# chip.net
KiCad netlist of a schematic drawn in EAGLE
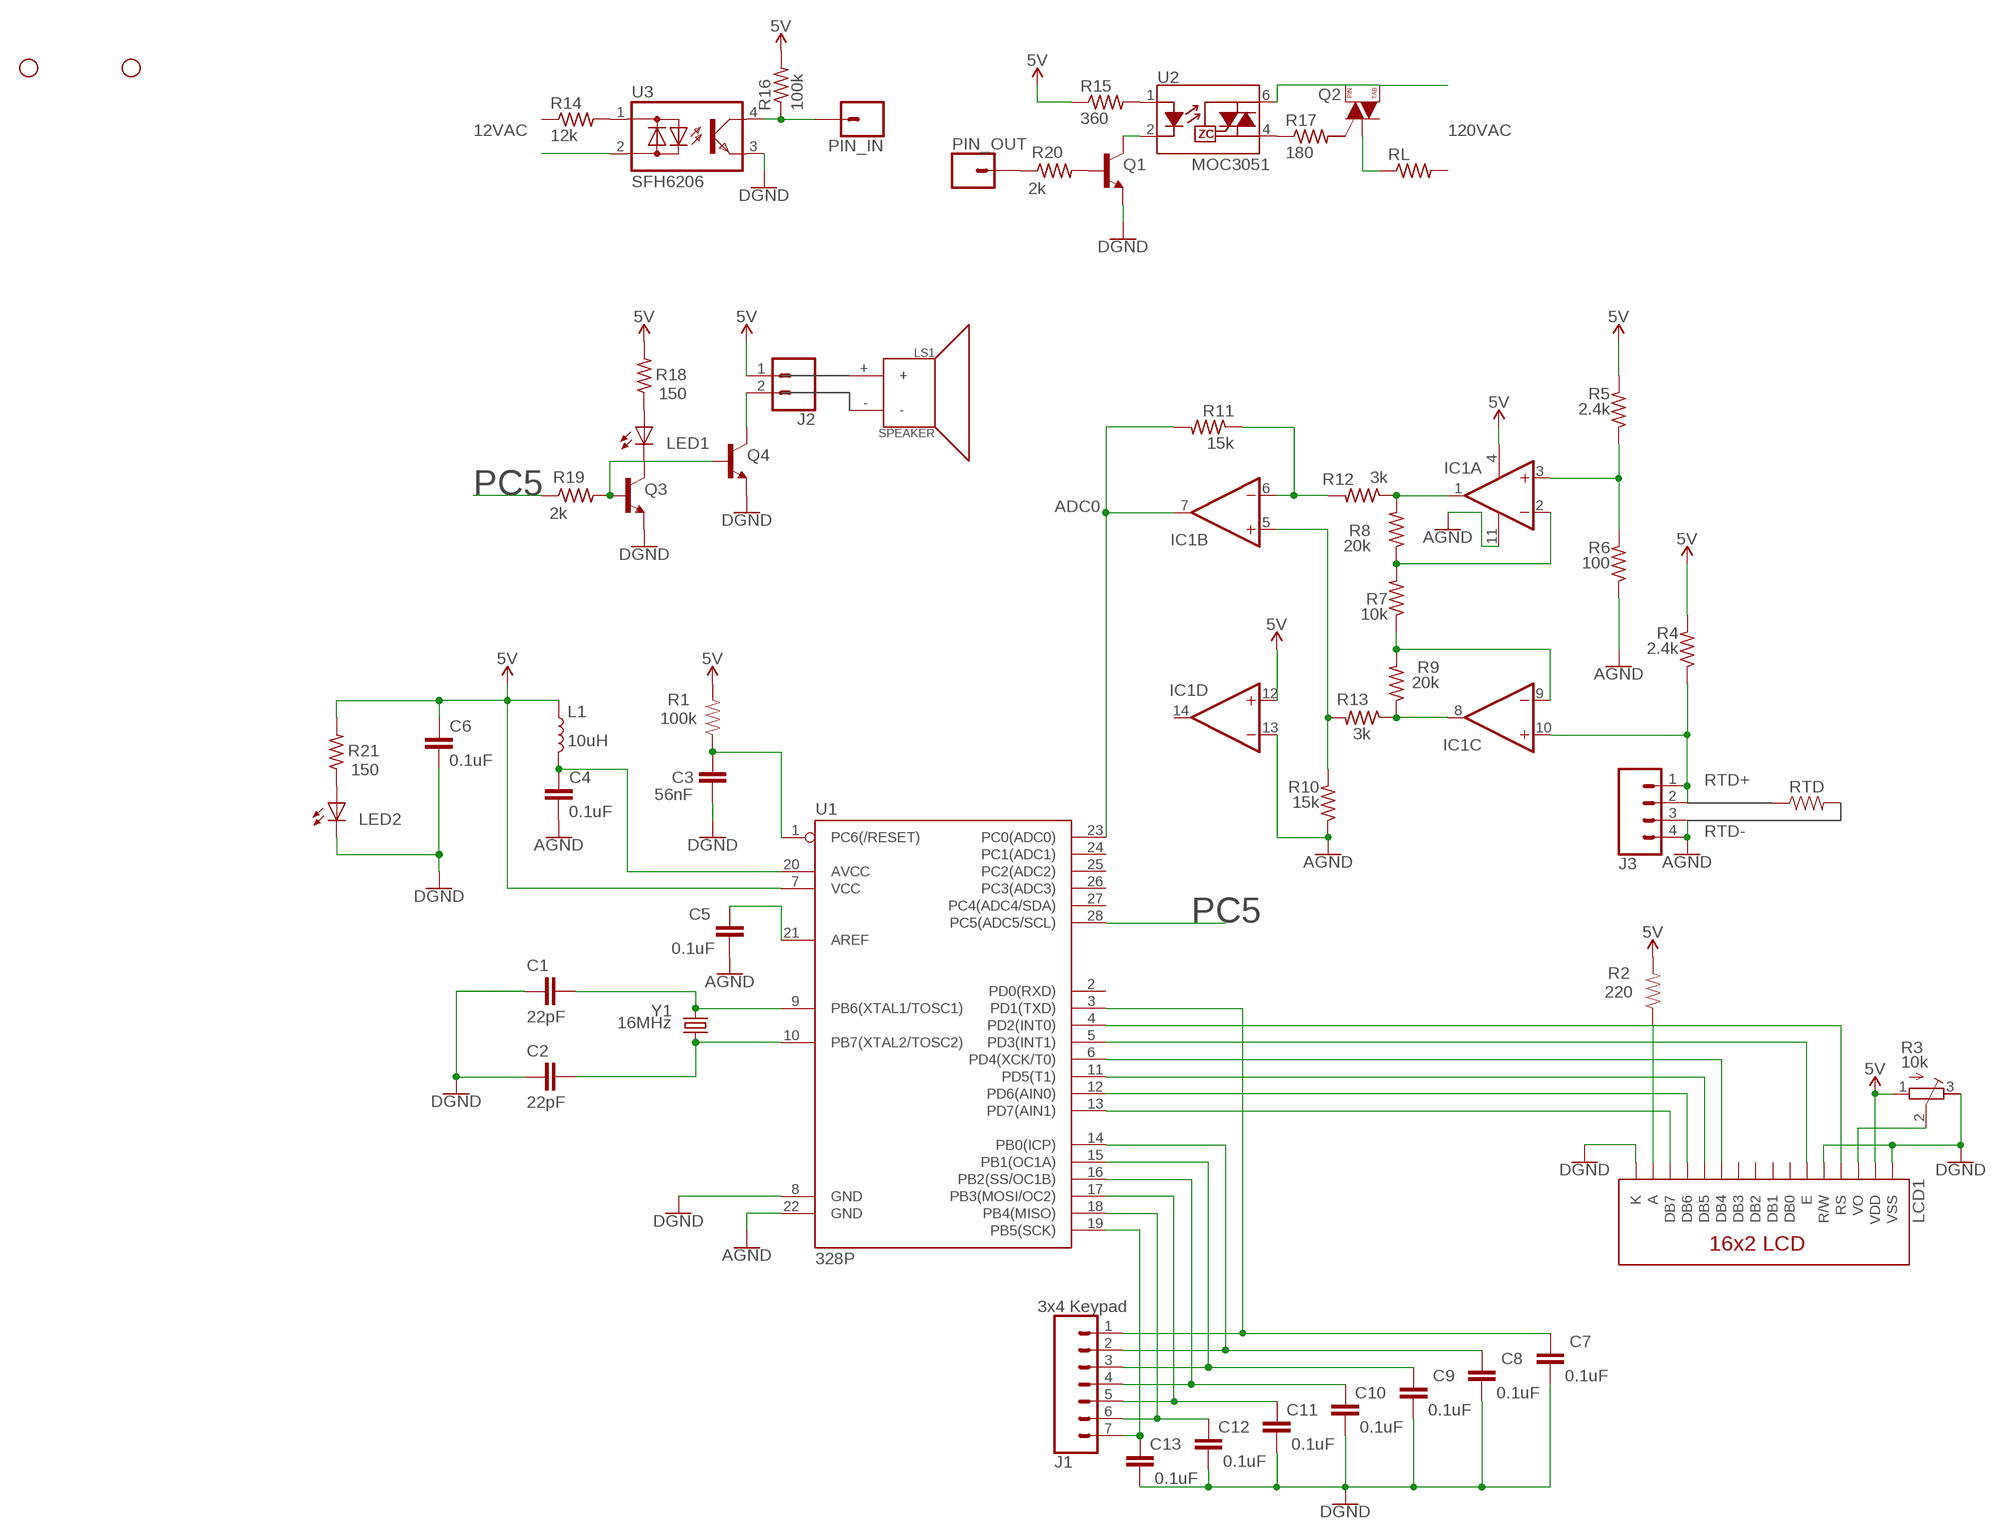
[diagram p0: schematic, sheet 1]

(export (version "E")
  (design (tool "Eeschema 10.0.6"))
  (components
    (comp (ref "C1")
      (value "22pF")
      (footprint "eagle-import:0603")
      (libsource (lib "eagle-import") (part "22PF-0603-50V-5%"))
    )
    (comp (ref "C2")
      (value "22pF")
      (footprint "eagle-import:0603")
      (libsource (lib "eagle-import") (part "22PF-0603-50V-5%"))
    )
    (comp (ref "C3")
      (value "56nF")
      (footprint "eagle-import:0603")
      (libsource (lib "eagle-import") (part "47NF-0603-25V-5%"))
    )
    (comp (ref "C4")
      (value "0.1uF")
      (footprint "eagle-import:0603")
      (libsource (lib "eagle-import") (part "0.1UF-0603-25V-(+80/-20%)"))
    )
    (comp (ref "C5")
      (value "0.1uF")
      (footprint "eagle-import:0603")
      (libsource (lib "eagle-import") (part "0.1UF-0603-25V-(+80/-20%)"))
    )
    (comp (ref "C6")
      (value "0.1uF")
      (footprint "eagle-import:0603")
      (libsource (lib "eagle-import") (part "0.1UF-0603-25V-(+80/-20%)"))
    )
    (comp (ref "C7")
      (value "0.1uF")
      (footprint "eagle-import:0603")
      (libsource (lib "eagle-import") (part "0.1UF-0603-25V-(+80/-20%)"))
    )
    (comp (ref "C8")
      (value "0.1uF")
      (footprint "eagle-import:0603")
      (libsource (lib "eagle-import") (part "0.1UF-0603-25V-(+80/-20%)"))
    )
    (comp (ref "C9")
      (value "0.1uF")
      (footprint "eagle-import:0603")
      (libsource (lib "eagle-import") (part "0.1UF-0603-25V-(+80/-20%)"))
    )
    (comp (ref "C10")
      (value "0.1uF")
      (footprint "eagle-import:0603")
      (libsource (lib "eagle-import") (part "0.1UF-0603-25V-(+80/-20%)"))
    )
    (comp (ref "C11")
      (value "0.1uF")
      (footprint "eagle-import:0603")
      (libsource (lib "eagle-import") (part "0.1UF-0603-25V-(+80/-20%)"))
    )
    (comp (ref "C12")
      (value "0.1uF")
      (footprint "eagle-import:0603")
      (libsource (lib "eagle-import") (part "0.1UF-0603-25V-(+80/-20%)"))
    )
    (comp (ref "C13")
      (value "0.1uF")
      (footprint "eagle-import:0603")
      (libsource (lib "eagle-import") (part "0.1UF-0603-25V-(+80/-20%)"))
    )
    (comp (ref "H10")
      (value "STAND-OFF")
      (footprint "eagle-import:STAND-OFF")
      (libsource (lib "eagle-import") (part "STAND-OFF"))
    )
    (comp (ref "H11")
      (value "STAND-OFF")
      (footprint "eagle-import:STAND-OFF")
      (libsource (lib "eagle-import") (part "STAND-OFF"))
    )
    (comp (ref "IC1")
      (value "MCP604SL")
      (footprint "eagle-import:SO14")
      (libsource (lib "eagle-import") (part "MCP604SL"))
    )
    (comp (ref "J1")
      (value "3x4 Keypad")
      (footprint "eagle-import:1X07")
      (libsource (lib "eagle-import") (part "CONN_07"))
    )
    (comp (ref "J2")
      (value "CONN_02")
      (footprint "eagle-import:1X02")
      (libsource (lib "eagle-import") (part "CONN_02"))
    )
    (comp (ref "J3")
      (value "CONN_04SCREW")
      (footprint "eagle-import:SCREWTERMINAL-3.5MM-4")
      (libsource (lib "eagle-import") (part "CONN_04SCREW"))
    )
    (comp (ref "L1")
      (value "10uH")
      (footprint "eagle-import:0603")
      (libsource (lib "eagle-import") (part "INDUCTOR-0603-33NH"))
    )
    (comp (ref "LCD1")
      (value "LCD-16X2NOHOLES")
      (footprint "eagle-import:LCD-16X2_NOHOLESNOSILK")
      (libsource (lib "eagle-import") (part "LCD-16X2NOHOLES"))
    )
    (comp (ref "LED1")
      (value "LED5MM")
      (footprint "eagle-import:LED5MM")
      (libsource (lib "eagle-import") (part "LED5MM"))
    )
    (comp (ref "LED2")
      (value "LED5MM")
      (footprint "eagle-import:LED5MM")
      (libsource (lib "eagle-import") (part "LED5MM"))
    )
    (comp (ref "LS1")
      (value "SPEAKER")
      (footprint "eagle-import:PCB_MOUNT_SPEAKER")
      (libsource (lib "eagle-import") (part "SPEAKER"))
    )
    (comp (ref "PIN_IN")
      (value "CONN_01")
      (footprint "eagle-import:1X01")
      (libsource (lib "eagle-import") (part "CONN_01"))
    )
    (comp (ref "PIN_OUT")
      (value "CONN_01")
      (footprint "eagle-import:1X01")
      (libsource (lib "eagle-import") (part "CONN_01"))
    )
    (comp (ref "Q1")
      (value "TRANS_NPN-MMBTA42")
      (footprint "eagle-import:SOT23-3")
      (libsource (lib "eagle-import") (part "TRANS_NPN-MMBTA42"))
    )
    (comp (ref "Q2")
      (value "BT137-600E")
      (footprint "eagle-import:SOT223")
      (libsource (lib "eagle-import") (part "TRIAC-Z0103MN"))
    )
    (comp (ref "Q3")
      (value "TRANS_NPN-MMBTA42")
      (footprint "eagle-import:SOT23-3")
      (libsource (lib "eagle-import") (part "TRANS_NPN-MMBTA42"))
    )
    (comp (ref "Q4")
      (value "TRANS_NPN-MMBTA42")
      (footprint "eagle-import:SOT23-3")
      (libsource (lib "eagle-import") (part "TRANS_NPN-MMBTA42"))
    )
    (comp (ref "R1")
      (value "100k")
      (footprint "eagle-import:0603")
      (libsource (lib "eagle-import") (part "10KOHM-0603-1/10W-1%"))
    )
    (comp (ref "R2")
      (value "220")
      (footprint "eagle-import:0603")
      (libsource (lib "eagle-import") (part "220OHM-0603-1/10W-1%"))
    )
    (comp (ref "R3")
      (value "10k")
      (footprint "eagle-import:RTRIM3296W")
      (libsource (lib "eagle-import") (part "R-TRIMM3296W"))
    )
    (comp (ref "R4")
      (value "2.4k")
      (footprint "eagle-import:R0603")
      (libsource (lib "eagle-import") (part "resistor_348_R-US_R0603"))
    )
    (comp (ref "R5")
      (value "2.4k")
      (footprint "eagle-import:R0603")
      (libsource (lib "eagle-import") (part "resistor_348_R-US_R0603"))
    )
    (comp (ref "R6")
      (value "100")
      (footprint "eagle-import:R0603")
      (libsource (lib "eagle-import") (part "resistor_348_R-US_R0603"))
    )
    (comp (ref "R7")
      (value "10k")
      (footprint "eagle-import:R0603")
      (libsource (lib "eagle-import") (part "resistor_348_R-US_R0603"))
    )
    (comp (ref "R8")
      (value "20k")
      (footprint "eagle-import:R0603")
      (libsource (lib "eagle-import") (part "resistor_348_R-US_R0603"))
    )
    (comp (ref "R9")
      (value "20k")
      (footprint "eagle-import:R0603")
      (libsource (lib "eagle-import") (part "resistor_348_R-US_R0603"))
    )
    (comp (ref "R10")
      (value "15k")
      (footprint "eagle-import:R0603")
      (libsource (lib "eagle-import") (part "resistor_348_R-US_R0603"))
    )
    (comp (ref "R11")
      (value "15k")
      (footprint "eagle-import:R0603")
      (libsource (lib "eagle-import") (part "resistor_348_R-US_R0603"))
    )
    (comp (ref "R12")
      (value "3k")
      (footprint "eagle-import:R0603")
      (libsource (lib "eagle-import") (part "resistor_348_R-US_R0603"))
    )
    (comp (ref "R13")
      (value "3k")
      (footprint "eagle-import:R0603")
      (libsource (lib "eagle-import") (part "resistor_348_R-US_R0603"))
    )
    (comp (ref "R14")
      (value "12k")
      (footprint "eagle-import:R0603")
      (libsource (lib "eagle-import") (part "R-US_R0603"))
    )
    (comp (ref "R15")
      (value "360")
      (footprint "eagle-import:R0603")
      (libsource (lib "eagle-import") (part "R-US_R0603"))
    )
    (comp (ref "R16")
      (value "100k")
      (footprint "eagle-import:R0603")
      (libsource (lib "eagle-import") (part "R-US_R0603"))
    )
    (comp (ref "R17")
      (value "180")
      (footprint "eagle-import:R0603")
      (libsource (lib "eagle-import") (part "R-US_R0603"))
    )
    (comp (ref "R18")
      (value "150")
      (footprint "eagle-import:R0603")
      (libsource (lib "eagle-import") (part "R-US_R0603"))
    )
    (comp (ref "R19")
      (value "2k")
      (footprint "eagle-import:R0603")
      (libsource (lib "eagle-import") (part "R-US_R0603"))
    )
    (comp (ref "R20")
      (value "2k")
      (footprint "eagle-import:R0603")
      (libsource (lib "eagle-import") (part "R-US_R0603"))
    )
    (comp (ref "R21")
      (value "150")
      (footprint "eagle-import:R0603")
      (libsource (lib "eagle-import") (part "R-US_R0603"))
    )
    (comp (ref "RL")
      (value "R-US_R0603")
      (footprint "eagle-import:R0603")
      (libsource (lib "eagle-import") (part "R-US_R0603"))
    )
    (comp (ref "RTD")
      (value "10KOHM-HORIZ-1/4W-1%")
      (footprint "eagle-import:AXIAL-0.3")
      (libsource (lib "eagle-import") (part "10KOHM-HORIZ-1/4W-1%"))
    )
    (comp (ref "U1")
      (value "328P")
      (footprint "eagle-import:DIP28")
      (libsource (lib "eagle-import") (part "ATMEGA328P_PDIP"))
    )
    (comp (ref "U2")
      (value "TRIAC_OPTOCOUPLER-MOC3063SM")
      (footprint "eagle-import:DIP8SMD")
      (libsource (lib "eagle-import") (part "TRIAC_OPTOCOUPLER-MOC3063SM"))
    )
    (comp (ref "U3")
      (value "SFH6206")
      (footprint "eagle-import:DIL4-SMD")
      (fields (field (name "MF") "VISHAY/TELEFUNKEN") (field (name "MPN") "SFH6206-3"))
      (libsource (lib "eagle-import") (part "SFH6206"))
    )
    (comp (ref "Y1")
      (value "16MHz")
      (footprint "eagle-import:HC49US")
      (libsource (lib "eagle-import") (part "CRYSTAL-16MHZPTH-HC49US"))
    )
  )
  (nets
    (net (code "1") (name "5V") (class "Default")
      (node (ref "C6") (pin "1") (pinfunction "1_1") (pintype "passive"))
      (node (ref "IC1") (pin "12") (pinfunction "+IN_12") (pintype "input"))
      (node (ref "IC1") (pin "4") (pinfunction "V+_4") (pintype "power_in"))
      (node (ref "J2") (pin "1") (pinfunction "1_1") (pintype "passive"))
      (node (ref "L1") (pin "1") (pinfunction "1_1") (pintype "passive"))
      (node (ref "LCD1") (pin "2") (pinfunction "VDD_2") (pintype "power_in"))
      (node (ref "R1") (pin "2") (pinfunction "2_2") (pintype "passive"))
      (node (ref "R15") (pin "1") (pinfunction "1_1") (pintype "passive"))
      (node (ref "R16") (pin "2") (pinfunction "2_2") (pintype "passive"))
      (node (ref "R18") (pin "2") (pinfunction "2_2") (pintype "passive"))
      (node (ref "R2") (pin "2") (pinfunction "2_2") (pintype "passive"))
      (node (ref "R21") (pin "2") (pinfunction "2_2") (pintype "passive"))
      (node (ref "R3") (pin "1") (pinfunction "A_1") (pintype "passive"))
      (node (ref "R4") (pin "2") (pinfunction "2_2") (pintype "passive"))
      (node (ref "R5") (pin "2") (pinfunction "2_2") (pintype "passive"))
      (node (ref "U1") (pin "7") (pinfunction "VCC_7") (pintype "bidirectional"))
    )
    (net (code "2") (name "AGND") (class "Default")
      (node (ref "C4") (pin "2") (pinfunction "2_2") (pintype "passive"))
      (node (ref "C5") (pin "2") (pinfunction "2_2") (pintype "passive"))
      (node (ref "IC1") (pin "11") (pinfunction "V-_11") (pintype "power_in"))
      (node (ref "IC1") (pin "13") (pinfunction "-IN_13") (pintype "input"))
      (node (ref "J3") (pin "3") (pinfunction "3_3") (pintype "passive"))
      (node (ref "J3") (pin "4") (pinfunction "4_4") (pintype "passive"))
      (node (ref "R10") (pin "1") (pinfunction "1_1") (pintype "passive"))
      (node (ref "R6") (pin "1") (pinfunction "1_1") (pintype "passive"))
      (node (ref "U1") (pin "22") (pinfunction "GND_22") (pintype "bidirectional"))
    )
    (net (code "3") (name "DGND") (class "Default")
      (node (ref "C1") (pin "1") (pinfunction "1_1") (pintype "passive"))
      (node (ref "C10") (pin "2") (pinfunction "2_2") (pintype "passive"))
      (node (ref "C11") (pin "2") (pinfunction "2_2") (pintype "passive"))
      (node (ref "C12") (pin "2") (pinfunction "2_2") (pintype "passive"))
      (node (ref "C13") (pin "2") (pinfunction "2_2") (pintype "passive"))
      (node (ref "C2") (pin "1") (pinfunction "1_1") (pintype "passive"))
      (node (ref "C3") (pin "2") (pinfunction "2_2") (pintype "passive"))
      (node (ref "C6") (pin "2") (pinfunction "2_2") (pintype "passive"))
      (node (ref "C7") (pin "2") (pinfunction "2_2") (pintype "passive"))
      (node (ref "C8") (pin "2") (pinfunction "2_2") (pintype "passive"))
      (node (ref "C9") (pin "2") (pinfunction "2_2") (pintype "passive"))
      (node (ref "LCD1") (pin "1") (pinfunction "VSS_1") (pintype "power_in"))
      (node (ref "LCD1") (pin "16") (pinfunction "K_16") (pintype "power_in"))
      (node (ref "LCD1") (pin "5") (pinfunction "R/W_5") (pintype "input"))
      (node (ref "LED2") (pin "K") (pinfunction "C_K") (pintype "passive"))
      (node (ref "Q1") (pin "2") (pinfunction "E_2") (pintype "passive"))
      (node (ref "Q3") (pin "2") (pinfunction "E_2") (pintype "passive"))
      (node (ref "Q4") (pin "2") (pinfunction "E_2") (pintype "passive"))
      (node (ref "R3") (pin "3") (pinfunction "E_3") (pintype "passive"))
      (node (ref "U1") (pin "8") (pinfunction "GND_8") (pintype "bidirectional"))
      (node (ref "U3") (pin "3") (pinfunction "E_3") (pintype "passive"))
    )
    (net (code "4") (name "Net-(IC1A-+IN)") (class "Default")
      (node (ref "IC1") (pin "3") (pinfunction "+IN_3") (pintype "input"))
      (node (ref "R5") (pin "1") (pinfunction "1_1") (pintype "passive"))
      (node (ref "R6") (pin "2") (pinfunction "2_2") (pintype "passive"))
    )
    (net (code "5") (name "Net-(IC1A--IN)") (class "Default")
      (node (ref "IC1") (pin "2") (pinfunction "-IN_2") (pintype "input"))
      (node (ref "R7") (pin "2") (pinfunction "2_2") (pintype "passive"))
      (node (ref "R8") (pin "1") (pinfunction "1_1") (pintype "passive"))
    )
    (net (code "6") (name "Net-(IC1A-OUT)") (class "Default")
      (node (ref "IC1") (pin "1") (pinfunction "OUT_1") (pintype "output"))
      (node (ref "R12") (pin "1") (pinfunction "1_1") (pintype "passive"))
      (node (ref "R8") (pin "2") (pinfunction "2_2") (pintype "passive"))
    )
    (net (code "7") (name "Net-(IC1B-+IN)") (class "Default")
      (node (ref "IC1") (pin "5") (pinfunction "+IN_5") (pintype "input"))
      (node (ref "R10") (pin "2") (pinfunction "2_2") (pintype "passive"))
      (node (ref "R13") (pin "2") (pinfunction "2_2") (pintype "passive"))
    )
    (net (code "8") (name "Net-(IC1B--IN)") (class "Default")
      (node (ref "IC1") (pin "6") (pinfunction "-IN_6") (pintype "input"))
      (node (ref "R11") (pin "1") (pinfunction "1_1") (pintype "passive"))
      (node (ref "R12") (pin "2") (pinfunction "2_2") (pintype "passive"))
    )
    (net (code "9") (name "Net-(IC1B-OUT)") (class "Default")
      (node (ref "IC1") (pin "7") (pinfunction "OUT_7") (pintype "output"))
      (node (ref "R11") (pin "2") (pinfunction "2_2") (pintype "passive"))
      (node (ref "U1") (pin "23") (pinfunction "PC0(ADC0)_23") (pintype "bidirectional"))
    )
    (net (code "10") (name "Net-(IC1C-+IN)") (class "Default")
      (node (ref "IC1") (pin "10") (pinfunction "+IN_10") (pintype "input"))
      (node (ref "J3") (pin "1") (pinfunction "1_1") (pintype "passive"))
      (node (ref "J3") (pin "2") (pinfunction "2_2") (pintype "passive"))
      (node (ref "R4") (pin "1") (pinfunction "1_1") (pintype "passive"))
    )
    (net (code "11") (name "Net-(IC1C--IN)") (class "Default")
      (node (ref "IC1") (pin "9") (pinfunction "-IN_9") (pintype "input"))
      (node (ref "R7") (pin "1") (pinfunction "1_1") (pintype "passive"))
      (node (ref "R9") (pin "2") (pinfunction "2_2") (pintype "passive"))
    )
    (net (code "12") (name "Net-(IC1C-OUT)") (class "Default")
      (node (ref "IC1") (pin "8") (pinfunction "OUT_8") (pintype "output"))
      (node (ref "R13") (pin "1") (pinfunction "1_1") (pintype "passive"))
      (node (ref "R9") (pin "1") (pinfunction "1_1") (pintype "passive"))
    )
    (net (code "13") (name "Net-(LCD1-A)") (class "Default")
      (node (ref "LCD1") (pin "15") (pinfunction "A_15") (pintype "power_in"))
      (node (ref "R2") (pin "1") (pinfunction "1_1") (pintype "passive"))
    )
    (net (code "14") (name "Net-(LCD1-DB4)") (class "Default")
      (node (ref "LCD1") (pin "11") (pinfunction "DB4_11") (pintype "bidirectional"))
      (node (ref "U1") (pin "6") (pinfunction "PD4(XCK/T0)_6") (pintype "bidirectional"))
    )
    (net (code "15") (name "Net-(LCD1-DB5)") (class "Default")
      (node (ref "LCD1") (pin "12") (pinfunction "DB5_12") (pintype "bidirectional"))
      (node (ref "U1") (pin "11") (pinfunction "PD5(T1)_11") (pintype "bidirectional"))
    )
    (net (code "16") (name "Net-(LCD1-DB6)") (class "Default")
      (node (ref "LCD1") (pin "13") (pinfunction "DB6_13") (pintype "bidirectional"))
      (node (ref "U1") (pin "12") (pinfunction "PD6(AIN0)_12") (pintype "bidirectional"))
    )
    (net (code "17") (name "Net-(LCD1-DB7)") (class "Default")
      (node (ref "LCD1") (pin "14") (pinfunction "DB7_14") (pintype "bidirectional"))
      (node (ref "U1") (pin "13") (pinfunction "PD7(AIN1)_13") (pintype "bidirectional"))
    )
    (net (code "18") (name "Net-(LCD1-E)") (class "Default")
      (node (ref "LCD1") (pin "6") (pinfunction "E_6") (pintype "input"))
      (node (ref "U1") (pin "5") (pinfunction "PD3(INT1)_5") (pintype "bidirectional"))
    )
    (net (code "19") (name "Net-(LCD1-RS)") (class "Default")
      (node (ref "LCD1") (pin "4") (pinfunction "RS_4") (pintype "input"))
      (node (ref "U1") (pin "4") (pinfunction "PD2(INT0)_4") (pintype "bidirectional"))
    )
    (net (code "20") (name "Net-(LCD1-VO)") (class "Default")
      (node (ref "LCD1") (pin "3") (pinfunction "VO_3") (pintype "bidirectional"))
      (node (ref "R3") (pin "2") (pinfunction "S_2") (pintype "passive"))
    )
    (net (code "21") (name "Net-(LED1-C)") (class "Default")
      (node (ref "LED1") (pin "K") (pinfunction "C_K") (pintype "passive"))
      (node (ref "Q3") (pin "3") (pinfunction "C_3") (pintype "passive"))
    )
    (net (code "22") (name "Net-(LED1-PadA)") (class "Default")
      (node (ref "LED1") (pin "A") (pinfunction "A_A") (pintype "passive"))
      (node (ref "R18") (pin "1") (pinfunction "1_1") (pintype "passive"))
    )
    (net (code "23") (name "Net-(LED2-PadA)") (class "Default")
      (node (ref "LED2") (pin "A") (pinfunction "A_A") (pintype "passive"))
      (node (ref "R21") (pin "1") (pinfunction "1_1") (pintype "passive"))
    )
    (net (code "24") (name "Net-(PIN_OUT-Pad1)") (class "Default")
      (node (ref "PIN_OUT") (pin "1") (pinfunction "1_1") (pintype "passive"))
      (node (ref "R20") (pin "1") (pinfunction "1_1") (pintype "passive"))
    )
    (net (code "25") (name "Net-(Q1-B)") (class "Default")
      (node (ref "Q1") (pin "1") (pinfunction "B_1") (pintype "passive"))
      (node (ref "R20") (pin "2") (pinfunction "2_2") (pintype "passive"))
    )
    (net (code "26") (name "Net-(Q1-C)") (class "Default")
      (node (ref "Q1") (pin "3") (pinfunction "C_3") (pintype "passive"))
      (node (ref "U2") (pin "2") (pinfunction "K_2") (pintype "bidirectional"))
    )
    (net (code "27") (name "Net-(Q2-T1)") (class "Default")
      (node (ref "Q2") (pin "1") (pinfunction "T1_1") (pintype "bidirectional"))
      (node (ref "RL") (pin "1") (pinfunction "1_1") (pintype "passive"))
    )
    (net (code "28") (name "Net-(Q3-B)") (class "Default")
      (node (ref "Q3") (pin "1") (pinfunction "B_1") (pintype "passive"))
      (node (ref "Q4") (pin "1") (pinfunction "B_1") (pintype "passive"))
      (node (ref "R19") (pin "2") (pinfunction "2_2") (pintype "passive"))
    )
    (net (code "29") (name "Net-(Q4-C)") (class "Default")
      (node (ref "J2") (pin "2") (pinfunction "2_2") (pintype "passive"))
      (node (ref "Q4") (pin "3") (pinfunction "C_3") (pintype "passive"))
    )
    (net (code "30") (name "Net-(U1-AREF)") (class "Default")
      (node (ref "C5") (pin "1") (pinfunction "1_1") (pintype "passive"))
      (node (ref "U1") (pin "21") (pinfunction "AREF_21") (pintype "bidirectional"))
    )
    (net (code "31") (name "Net-(U1-AVCC)") (class "Default")
      (node (ref "C4") (pin "1") (pinfunction "1_1") (pintype "passive"))
      (node (ref "L1") (pin "2") (pinfunction "2_2") (pintype "passive"))
      (node (ref "U1") (pin "20") (pinfunction "AVCC_20") (pintype "bidirectional"))
    )
    (net (code "32") (name "Net-(U1-PB0(ICP))") (class "Default")
      (node (ref "C8") (pin "1") (pinfunction "1_1") (pintype "passive"))
      (node (ref "J1") (pin "2") (pinfunction "2_2") (pintype "passive"))
      (node (ref "U1") (pin "14") (pinfunction "PB0(ICP)_14") (pintype "bidirectional"))
    )
    (net (code "33") (name "Net-(U1-PB1(OC1A))") (class "Default")
      (node (ref "C9") (pin "1") (pinfunction "1_1") (pintype "passive"))
      (node (ref "J1") (pin "3") (pinfunction "3_3") (pintype "passive"))
      (node (ref "U1") (pin "15") (pinfunction "PB1(OC1A)_15") (pintype "bidirectional"))
    )
    (net (code "34") (name "Net-(U1-PB2(SS{slash}OC1B))") (class "Default")
      (node (ref "C10") (pin "1") (pinfunction "1_1") (pintype "passive"))
      (node (ref "J1") (pin "4") (pinfunction "4_4") (pintype "passive"))
      (node (ref "U1") (pin "16") (pinfunction "PB2(SS/OC1B)_16") (pintype "bidirectional"))
    )
    (net (code "35") (name "Net-(U1-PB3(MOSI{slash}OC2))") (class "Default")
      (node (ref "C11") (pin "1") (pinfunction "1_1") (pintype "passive"))
      (node (ref "J1") (pin "5") (pinfunction "5_5") (pintype "passive"))
      (node (ref "U1") (pin "17") (pinfunction "PB3(MOSI/OC2)_17") (pintype "bidirectional"))
    )
    (net (code "36") (name "Net-(U1-PB4(MISO))") (class "Default")
      (node (ref "C12") (pin "1") (pinfunction "1_1") (pintype "passive"))
      (node (ref "J1") (pin "6") (pinfunction "6_6") (pintype "passive"))
      (node (ref "U1") (pin "18") (pinfunction "PB4(MISO)_18") (pintype "bidirectional"))
    )
    (net (code "37") (name "Net-(U1-PB5(SCK))") (class "Default")
      (node (ref "C13") (pin "1") (pinfunction "1_1") (pintype "passive"))
      (node (ref "J1") (pin "7") (pinfunction "7_7") (pintype "passive"))
      (node (ref "U1") (pin "19") (pinfunction "PB5(SCK)_19") (pintype "bidirectional"))
    )
    (net (code "38") (name "Net-(U1-PB6(XTAL1{slash}TOSC1))") (class "Default")
      (node (ref "C1") (pin "2") (pinfunction "2_2") (pintype "passive"))
      (node (ref "U1") (pin "9") (pinfunction "PB6(XTAL1/TOSC1)_9") (pintype "bidirectional"))
      (node (ref "Y1") (pin "2") (pinfunction "2_2") (pintype "passive"))
    )
    (net (code "39") (name "Net-(U1-PB7(XTAL2{slash}TOSC2))") (class "Default")
      (node (ref "C2") (pin "2") (pinfunction "2_2") (pintype "passive"))
      (node (ref "U1") (pin "10") (pinfunction "PB7(XTAL2/TOSC2)_10") (pintype "bidirectional"))
      (node (ref "Y1") (pin "1") (pinfunction "1_1") (pintype "passive"))
    )
    (net (code "40") (name "Net-(U1-PC6({slash}RESET))") (class "Default")
      (node (ref "C3") (pin "1") (pinfunction "1_1") (pintype "passive"))
      (node (ref "R1") (pin "1") (pinfunction "1_1") (pintype "passive"))
      (node (ref "U1") (pin "1") (pinfunction "PC6(/RESET)_1") (pintype "bidirectional"))
    )
    (net (code "41") (name "Net-(U1-PD1(TXD))") (class "Default")
      (node (ref "C7") (pin "1") (pinfunction "1_1") (pintype "passive"))
      (node (ref "J1") (pin "1") (pinfunction "1_1") (pintype "passive"))
      (node (ref "U1") (pin "3") (pinfunction "PD1(TXD)_3") (pintype "bidirectional"))
    )
    (net (code "42") (name "Net-(U2-A)") (class "Default")
      (node (ref "R15") (pin "2") (pinfunction "2_2") (pintype "passive"))
      (node (ref "U2") (pin "1") (pinfunction "A_1") (pintype "bidirectional"))
    )
    (net (code "43") (name "Net-(U2-T1)") (class "Default")
      (node (ref "Q2") (pin "2") (pinfunction "T2_2") (pintype "passive"))
      (node (ref "Q2") (pin "4") (pinfunction "T2_4") (pintype "passive"))
      (node (ref "U2") (pin "6") (pinfunction "T1_6") (pintype "bidirectional"))
    )
    (net (code "44") (name "Net-(U2-T2)") (class "Default")
      (node (ref "R17") (pin "1") (pinfunction "1_1") (pintype "passive"))
      (node (ref "U2") (pin "4") (pinfunction "T2_4") (pintype "bidirectional"))
    )
    (net (code "45") (name "Net-(U3-AC1)") (class "Default")
      (node (ref "R14") (pin "2") (pinfunction "2_2") (pintype "passive"))
      (node (ref "U3") (pin "1") (pinfunction "AC1_1") (pintype "passive"))
    )
    (net (code "46") (name "Net-(U3-C)") (class "Default")
      (node (ref "PIN_IN") (pin "1") (pinfunction "1_1") (pintype "passive"))
      (node (ref "R16") (pin "1") (pinfunction "1_1") (pintype "passive"))
      (node (ref "U3") (pin "4") (pinfunction "C_4") (pintype "passive"))
    )
    (net (code "47") (name "unconnected-(IC1D-OUT-Pad14)") (class "Default")
      (node (ref "IC1") (pin "14") (pinfunction "OUT_14") (pintype "output"))
    )
    (net (code "48") (name "unconnected-(LCD1-DB0-Pad7)") (class "Default")
      (node (ref "LCD1") (pin "7") (pinfunction "DB0_7") (pintype "bidirectional"))
    )
    (net (code "49") (name "unconnected-(LCD1-DB1-Pad8)") (class "Default")
      (node (ref "LCD1") (pin "8") (pinfunction "DB1_8") (pintype "bidirectional"))
    )
    (net (code "50") (name "unconnected-(LCD1-DB2-Pad9)") (class "Default")
      (node (ref "LCD1") (pin "9") (pinfunction "DB2_9") (pintype "bidirectional"))
    )
    (net (code "51") (name "unconnected-(LCD1-DB3-Pad10)") (class "Default")
      (node (ref "LCD1") (pin "10") (pinfunction "DB3_10") (pintype "bidirectional"))
    )
    (net (code "52") (name "unconnected-(LS1-Pad+)") (class "Default")
      (node (ref "LS1") (pin "+") (pinfunction "+_+") (pintype "bidirectional"))
    )
    (net (code "53") (name "unconnected-(LS1-Pad-)") (class "Default")
      (node (ref "LS1") (pin "-") (pinfunction "-_-") (pintype "bidirectional"))
    )
    (net (code "54") (name "unconnected-(Q2-G-Pad3)") (class "Default")
      (node (ref "Q2") (pin "3") (pinfunction "G_3") (pintype "bidirectional"))
    )
    (net (code "55") (name "unconnected-(R14-Pad1)") (class "Default")
      (node (ref "R14") (pin "1") (pinfunction "1_1") (pintype "passive"))
    )
    (net (code "56") (name "unconnected-(R17-Pad2)") (class "Default")
      (node (ref "R17") (pin "2") (pinfunction "2_2") (pintype "passive"))
    )
    (net (code "57") (name "unconnected-(R19-Pad1)") (class "Default")
      (node (ref "R19") (pin "1") (pinfunction "1_1") (pintype "passive"))
    )
    (net (code "58") (name "unconnected-(RL-Pad2)") (class "Default")
      (node (ref "RL") (pin "2") (pinfunction "2_2") (pintype "passive"))
    )
    (net (code "59") (name "unconnected-(RTD-1-PadP$1)") (class "Default")
      (node (ref "RTD") (pin "P$1") (pinfunction "1_P$1") (pintype "passive"))
    )
    (net (code "60") (name "unconnected-(RTD-2-PadP$2)") (class "Default")
      (node (ref "RTD") (pin "P$2") (pinfunction "2_P$2") (pintype "passive"))
    )
    (net (code "61") (name "unconnected-(U1-PC1(ADC1)-Pad24)") (class "Default")
      (node (ref "U1") (pin "24") (pinfunction "PC1(ADC1)_24") (pintype "bidirectional"))
    )
    (net (code "62") (name "unconnected-(U1-PC2(ADC2)-Pad25)") (class "Default")
      (node (ref "U1") (pin "25") (pinfunction "PC2(ADC2)_25") (pintype "bidirectional"))
    )
    (net (code "63") (name "unconnected-(U1-PC3(ADC3)-Pad26)") (class "Default")
      (node (ref "U1") (pin "26") (pinfunction "PC3(ADC3)_26") (pintype "bidirectional"))
    )
    (net (code "64") (name "unconnected-(U1-PC4(ADC4{slash}SDA)-Pad27)") (class "Default")
      (node (ref "U1") (pin "27") (pinfunction "PC4(ADC4/SDA)_27") (pintype "bidirectional"))
    )
    (net (code "65") (name "unconnected-(U1-PC5(ADC5{slash}SCL)-Pad28)") (class "Default")
      (node (ref "U1") (pin "28") (pinfunction "PC5(ADC5/SCL)_28") (pintype "bidirectional"))
    )
    (net (code "66") (name "unconnected-(U1-PD0(RXD)-Pad2)") (class "Default")
      (node (ref "U1") (pin "2") (pinfunction "PD0(RXD)_2") (pintype "bidirectional"))
    )
    (net (code "67") (name "unconnected-(U3-AC2-Pad2)") (class "Default")
      (node (ref "U3") (pin "2") (pinfunction "AC2_2") (pintype "passive"))
    )
  )
)
